# spedo_pcb_1.net
KiCad netlist of a schematic drawn in EAGLE
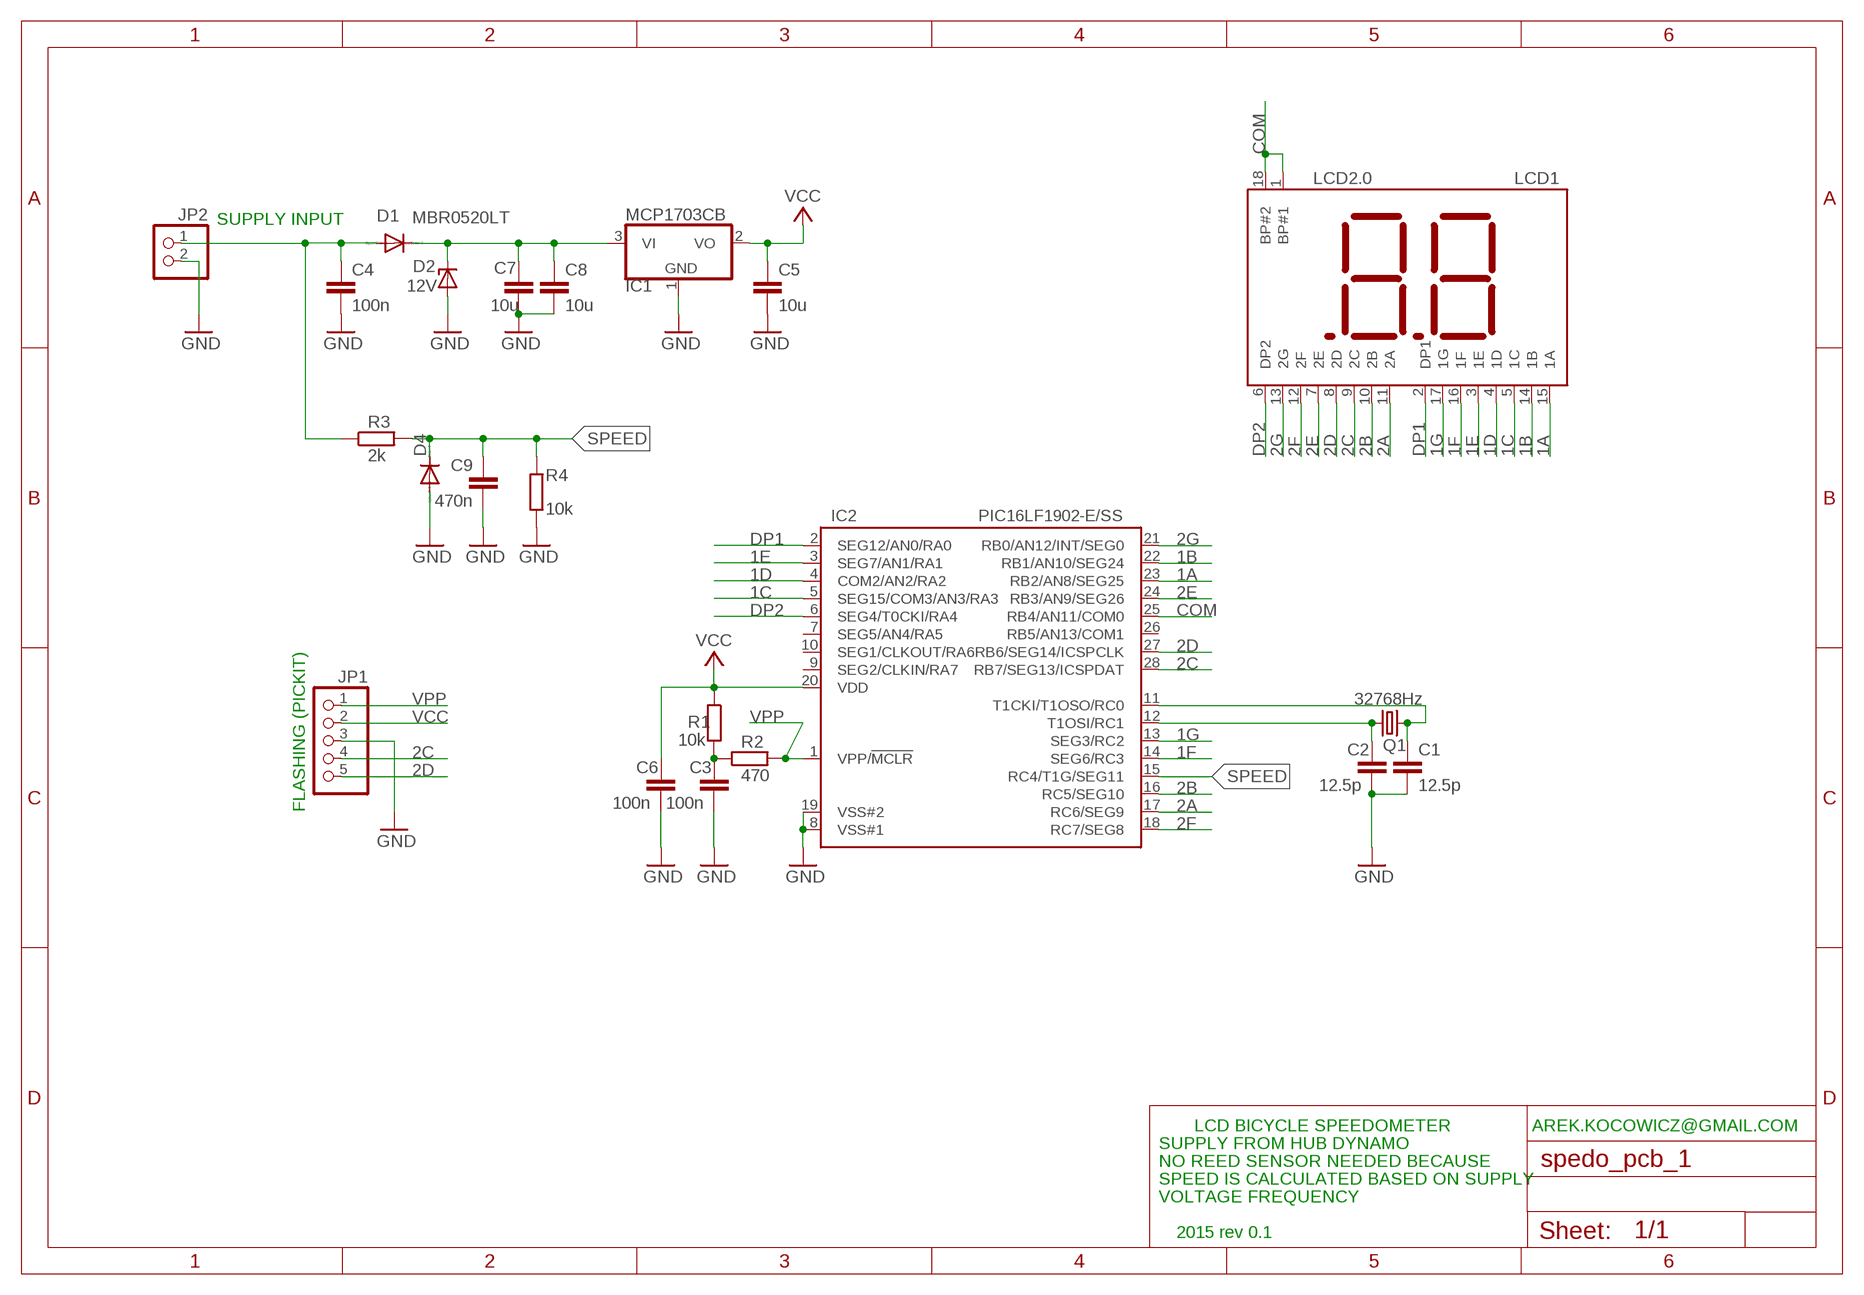
[diagram p0: schematic, sheet 1]

(export (version "E")
  (design (tool "Eeschema 10.0.6"))
  (components
    (comp (ref "C1")
      (value "12.5p")
      (footprint "eagle-import:C0603K")
      (libsource (lib "eagle-import") (part "C-EUC0603K"))
    )
    (comp (ref "C2")
      (value "12.5p")
      (footprint "eagle-import:C0603K")
      (libsource (lib "eagle-import") (part "C-EUC0603K"))
    )
    (comp (ref "C3")
      (value "100n")
      (footprint "eagle-import:C0603K")
      (libsource (lib "eagle-import") (part "C-EUC0603K"))
    )
    (comp (ref "C4")
      (value "100n")
      (footprint "eagle-import:C0603K")
      (libsource (lib "eagle-import") (part "C-EUC0603K"))
    )
    (comp (ref "C5")
      (value "10u")
      (footprint "eagle-import:C0805K")
      (libsource (lib "eagle-import") (part "C-EUC0805K"))
    )
    (comp (ref "C6")
      (value "100n")
      (footprint "eagle-import:C0603K")
      (libsource (lib "eagle-import") (part "C-EUC0603K"))
    )
    (comp (ref "C7")
      (value "10u")
      (footprint "eagle-import:C0805K")
      (libsource (lib "eagle-import") (part "C-EUC0805K"))
    )
    (comp (ref "C8")
      (value "10u")
      (footprint "eagle-import:C0805K")
      (libsource (lib "eagle-import") (part "C-EUC0805K"))
    )
    (comp (ref "C9")
      (value "470n")
      (footprint "eagle-import:C0603K")
      (libsource (lib "eagle-import") (part "C-EUC0603K"))
    )
    (comp (ref "D1")
      (value "MBR0520LT")
      (footprint "eagle-import:SOD123")
      (libsource (lib "eagle-import") (part "MBR0520LT"))
    )
    (comp (ref "D2")
      (value "12V")
      (footprint "eagle-import:SOD80C")
      (libsource (lib "eagle-import") (part "ZENER-DIODESOD80C"))
    )
    (comp (ref "D4")
      (value "DIODE-SOD323-W")
      (footprint "eagle-import:SOD323-W")
      (libsource (lib "eagle-import") (part "DIODE-SOD323-W"))
    )
    (comp (ref "IC1")
      (value "MCP1703CB")
      (footprint "eagle-import:SOT23")
      (libsource (lib "eagle-import") (part "MCP1703CB"))
    )
    (comp (ref "IC2")
      (value "PIC16LF1902-E/SS")
      (footprint "eagle-import:SSOP28")
      (libsource (lib "eagle-import") (part "PIC16LF1902-E/SS"))
    )
    (comp (ref "JP1")
      (value "PINHD-1X5/90")
      (footprint "eagle-import:1X05_90")
      (libsource (lib "eagle-import") (part "PINHD-1X5/90"))
    )
    (comp (ref "JP2")
      (value "PINHD-1X2")
      (footprint "eagle-import:1X02")
      (libsource (lib "eagle-import") (part "PINHD-1X2"))
    )
    (comp (ref "LCD1")
      (value "LCD2.0")
      (footprint "eagle-import:LCD2.0")
      (libsource (lib "eagle-import") (part "LCD2.0"))
    )
    (comp (ref "Q1")
      (value "32768Hz")
      (footprint "eagle-import:TC26H")
      (libsource (lib "eagle-import") (part "CRYSTALTC26H"))
    )
    (comp (ref "R1")
      (value "10k")
      (footprint "eagle-import:R0603")
      (libsource (lib "eagle-import") (part "R-EU_R0603"))
    )
    (comp (ref "R2")
      (value "470")
      (footprint "eagle-import:R0603")
      (libsource (lib "eagle-import") (part "R-EU_R0603"))
    )
    (comp (ref "R3")
      (value "2k")
      (footprint "eagle-import:R0603")
      (libsource (lib "eagle-import") (part "R-EU_R0603"))
    )
    (comp (ref "R4")
      (value "10k")
      (footprint "eagle-import:R0603")
      (libsource (lib "eagle-import") (part "R-EU_R0603"))
    )
  )
  (nets
    (net (code "1") (name "/1A") (class "Default")
      (node (ref "IC2") (pin "23") (pinfunction "RB2/AN8/SEG25_23") (pintype "bidirectional"))
      (node (ref "LCD1") (pin "15") (pinfunction "1A_15") (pintype "bidirectional"))
    )
    (net (code "2") (name "/1B") (class "Default")
      (node (ref "IC2") (pin "22") (pinfunction "RB1/AN10/SEG24_22") (pintype "bidirectional"))
      (node (ref "LCD1") (pin "14") (pinfunction "1B_14") (pintype "bidirectional"))
    )
    (net (code "3") (name "/1C") (class "Default")
      (node (ref "IC2") (pin "5") (pinfunction "SEG15/COM3/AN3/RA3_5") (pintype "bidirectional"))
      (node (ref "LCD1") (pin "5") (pinfunction "1C_5") (pintype "bidirectional"))
    )
    (net (code "4") (name "/1D") (class "Default")
      (node (ref "IC2") (pin "4") (pinfunction "COM2/AN2/RA2_4") (pintype "bidirectional"))
      (node (ref "LCD1") (pin "4") (pinfunction "1D_4") (pintype "bidirectional"))
    )
    (net (code "5") (name "/1E") (class "Default")
      (node (ref "IC2") (pin "3") (pinfunction "SEG7/AN1/RA1_3") (pintype "bidirectional"))
      (node (ref "LCD1") (pin "3") (pinfunction "1E_3") (pintype "bidirectional"))
    )
    (net (code "6") (name "/1F") (class "Default")
      (node (ref "IC2") (pin "14") (pinfunction "SEG6/RC3_14") (pintype "bidirectional"))
      (node (ref "LCD1") (pin "16") (pinfunction "1F_16") (pintype "bidirectional"))
    )
    (net (code "7") (name "/1G") (class "Default")
      (node (ref "IC2") (pin "13") (pinfunction "SEG3/RC2_13") (pintype "bidirectional"))
      (node (ref "LCD1") (pin "17") (pinfunction "1G_17") (pintype "bidirectional"))
    )
    (net (code "8") (name "/2A") (class "Default")
      (node (ref "IC2") (pin "17") (pinfunction "RC6/SEG9_17") (pintype "bidirectional"))
      (node (ref "LCD1") (pin "11") (pinfunction "2A_11") (pintype "bidirectional"))
    )
    (net (code "9") (name "/2B") (class "Default")
      (node (ref "IC2") (pin "16") (pinfunction "RC5/SEG10_16") (pintype "bidirectional"))
      (node (ref "LCD1") (pin "10") (pinfunction "2B_10") (pintype "bidirectional"))
    )
    (net (code "10") (name "/2C") (class "Default")
      (node (ref "IC2") (pin "28") (pinfunction "RB7/SEG13/ICSPDAT_28") (pintype "bidirectional"))
      (node (ref "JP1") (pin "4") (pinfunction "4_4") (pintype "passive"))
      (node (ref "LCD1") (pin "9") (pinfunction "2C_9") (pintype "bidirectional"))
    )
    (net (code "11") (name "/2D") (class "Default")
      (node (ref "IC2") (pin "27") (pinfunction "RB6/SEG14/ICSPCLK_27") (pintype "bidirectional"))
      (node (ref "JP1") (pin "5") (pinfunction "5_5") (pintype "passive"))
      (node (ref "LCD1") (pin "8") (pinfunction "2D_8") (pintype "bidirectional"))
    )
    (net (code "12") (name "/2E") (class "Default")
      (node (ref "IC2") (pin "24") (pinfunction "RB3/AN9/SEG26_24") (pintype "bidirectional"))
      (node (ref "LCD1") (pin "7") (pinfunction "2E_7") (pintype "bidirectional"))
    )
    (net (code "13") (name "/2F") (class "Default")
      (node (ref "IC2") (pin "18") (pinfunction "RC7/SEG8_18") (pintype "bidirectional"))
      (node (ref "LCD1") (pin "12") (pinfunction "2F_12") (pintype "bidirectional"))
    )
    (net (code "14") (name "/2G") (class "Default")
      (node (ref "IC2") (pin "21") (pinfunction "RB0/AN12/INT/SEG0_21") (pintype "bidirectional"))
      (node (ref "LCD1") (pin "13") (pinfunction "2G_13") (pintype "bidirectional"))
    )
    (net (code "15") (name "/COM") (class "Default")
      (node (ref "IC2") (pin "25") (pinfunction "RB4/AN11/COM0_25") (pintype "bidirectional"))
      (node (ref "LCD1") (pin "1") (pinfunction "BP#1_1") (pintype "bidirectional"))
      (node (ref "LCD1") (pin "18") (pinfunction "BP#2_18") (pintype "bidirectional"))
    )
    (net (code "16") (name "/DP1") (class "Default")
      (node (ref "IC2") (pin "2") (pinfunction "SEG12/AN0/RA0_2") (pintype "bidirectional"))
      (node (ref "LCD1") (pin "2") (pinfunction "DP1_2") (pintype "bidirectional"))
    )
    (net (code "17") (name "/DP2") (class "Default")
      (node (ref "IC2") (pin "6") (pinfunction "SEG4/T0CKI/RA4_6") (pintype "bidirectional"))
      (node (ref "LCD1") (pin "6") (pinfunction "DP2_6") (pintype "bidirectional"))
    )
    (net (code "18") (name "/VPP") (class "Default")
      (node (ref "IC2") (pin "1") (pinfunction "VPP/~{MCLR}_1") (pintype "bidirectional"))
      (node (ref "JP1") (pin "1") (pinfunction "1_1") (pintype "passive"))
      (node (ref "R2") (pin "2") (pinfunction "2_2") (pintype "passive"))
    )
    (net (code "19") (name "GND") (class "Default")
      (node (ref "C1") (pin "2") (pinfunction "2_2") (pintype "passive"))
      (node (ref "C2") (pin "2") (pinfunction "2_2") (pintype "passive"))
      (node (ref "C3") (pin "2") (pinfunction "2_2") (pintype "passive"))
      (node (ref "C4") (pin "2") (pinfunction "2_2") (pintype "passive"))
      (node (ref "C5") (pin "2") (pinfunction "2_2") (pintype "passive"))
      (node (ref "C6") (pin "2") (pinfunction "2_2") (pintype "passive"))
      (node (ref "C7") (pin "2") (pinfunction "2_2") (pintype "passive"))
      (node (ref "C8") (pin "2") (pinfunction "2_2") (pintype "passive"))
      (node (ref "C9") (pin "2") (pinfunction "2_2") (pintype "passive"))
      (node (ref "D2") (pin "A") (pinfunction "A_A") (pintype "passive"))
      (node (ref "D4") (pin "A") (pinfunction "A_A") (pintype "passive"))
      (node (ref "IC1") (pin "1") (pinfunction "GND_1") (pintype "passive"))
      (node (ref "IC2") (pin "19") (pinfunction "VSS#2_19") (pintype "bidirectional"))
      (node (ref "IC2") (pin "8") (pinfunction "VSS#1_8") (pintype "bidirectional"))
      (node (ref "JP1") (pin "3") (pinfunction "3_3") (pintype "passive"))
      (node (ref "JP2") (pin "2") (pinfunction "2_2") (pintype "passive"))
      (node (ref "R4") (pin "2") (pinfunction "2_2") (pintype "passive"))
    )
    (net (code "20") (name "Net-(C3-Pad1)") (class "Default")
      (node (ref "C3") (pin "1") (pinfunction "1_1") (pintype "passive"))
      (node (ref "R1") (pin "2") (pinfunction "2_2") (pintype "passive"))
      (node (ref "R2") (pin "1") (pinfunction "1_1") (pintype "passive"))
    )
    (net (code "21") (name "Net-(C4-Pad1)") (class "Default")
      (node (ref "C4") (pin "1") (pinfunction "1_1") (pintype "passive"))
      (node (ref "D1") (pin "A") (pinfunction "A_A") (pintype "passive"))
      (node (ref "JP2") (pin "1") (pinfunction "1_1") (pintype "passive"))
      (node (ref "R3") (pin "1") (pinfunction "1_1") (pintype "passive"))
    )
    (net (code "22") (name "Net-(IC1-VI)") (class "Default")
      (node (ref "C7") (pin "1") (pinfunction "1_1") (pintype "passive"))
      (node (ref "C8") (pin "1") (pinfunction "1_1") (pintype "passive"))
      (node (ref "D1") (pin "C") (pinfunction "C_C") (pintype "passive"))
      (node (ref "D2") (pin "C") (pinfunction "C_C") (pintype "passive"))
      (node (ref "IC1") (pin "3") (pinfunction "VI_3") (pintype "input"))
    )
    (net (code "23") (name "Net-(IC2-T1CKI{slash}T1OSO{slash}RC0)") (class "Default")
      (node (ref "C1") (pin "1") (pinfunction "1_1") (pintype "passive"))
      (node (ref "IC2") (pin "11") (pinfunction "T1CKI/T1OSO/RC0_11") (pintype "bidirectional"))
      (node (ref "Q1") (pin "2") (pinfunction "2_2") (pintype "passive"))
    )
    (net (code "24") (name "Net-(IC2-T1OSI{slash}RC1)") (class "Default")
      (node (ref "C2") (pin "1") (pinfunction "1_1") (pintype "passive"))
      (node (ref "IC2") (pin "12") (pinfunction "T1OSI/RC1_12") (pintype "bidirectional"))
      (node (ref "Q1") (pin "1") (pinfunction "1_1") (pintype "passive"))
    )
    (net (code "25") (name "SPEED") (class "Default")
      (node (ref "C9") (pin "1") (pinfunction "1_1") (pintype "passive"))
      (node (ref "D4") (pin "C") (pinfunction "C_C") (pintype "passive"))
      (node (ref "IC2") (pin "15") (pinfunction "RC4/T1G/SEG11_15") (pintype "bidirectional"))
      (node (ref "R3") (pin "2") (pinfunction "2_2") (pintype "passive"))
      (node (ref "R4") (pin "1") (pinfunction "1_1") (pintype "passive"))
    )
    (net (code "26") (name "VCC") (class "Default")
      (node (ref "C5") (pin "1") (pinfunction "1_1") (pintype "passive"))
      (node (ref "C6") (pin "1") (pinfunction "1_1") (pintype "passive"))
      (node (ref "IC1") (pin "2") (pinfunction "VO_2") (pintype "passive"))
      (node (ref "IC2") (pin "20") (pinfunction "VDD_20") (pintype "bidirectional"))
      (node (ref "JP1") (pin "2") (pinfunction "2_2") (pintype "passive"))
      (node (ref "R1") (pin "1") (pinfunction "1_1") (pintype "passive"))
    )
    (net (code "27") (name "unconnected-(IC2-RB5{slash}AN13{slash}COM1-Pad26)") (class "Default")
      (node (ref "IC2") (pin "26") (pinfunction "RB5/AN13/COM1_26") (pintype "bidirectional"))
    )
    (net (code "28") (name "unconnected-(IC2-SEG1{slash}CLKOUT{slash}RA6-Pad10)") (class "Default")
      (node (ref "IC2") (pin "10") (pinfunction "SEG1/CLKOUT/RA6_10") (pintype "bidirectional"))
    )
    (net (code "29") (name "unconnected-(IC2-SEG2{slash}CLKIN{slash}RA7-Pad9)") (class "Default")
      (node (ref "IC2") (pin "9") (pinfunction "SEG2/CLKIN/RA7_9") (pintype "bidirectional"))
    )
    (net (code "30") (name "unconnected-(IC2-SEG5{slash}AN4{slash}RA5-Pad7)") (class "Default")
      (node (ref "IC2") (pin "7") (pinfunction "SEG5/AN4/RA5_7") (pintype "bidirectional"))
    )
  )
)
